# Channel.net
KiCad netlist of a schematic drawn in Altium Designer
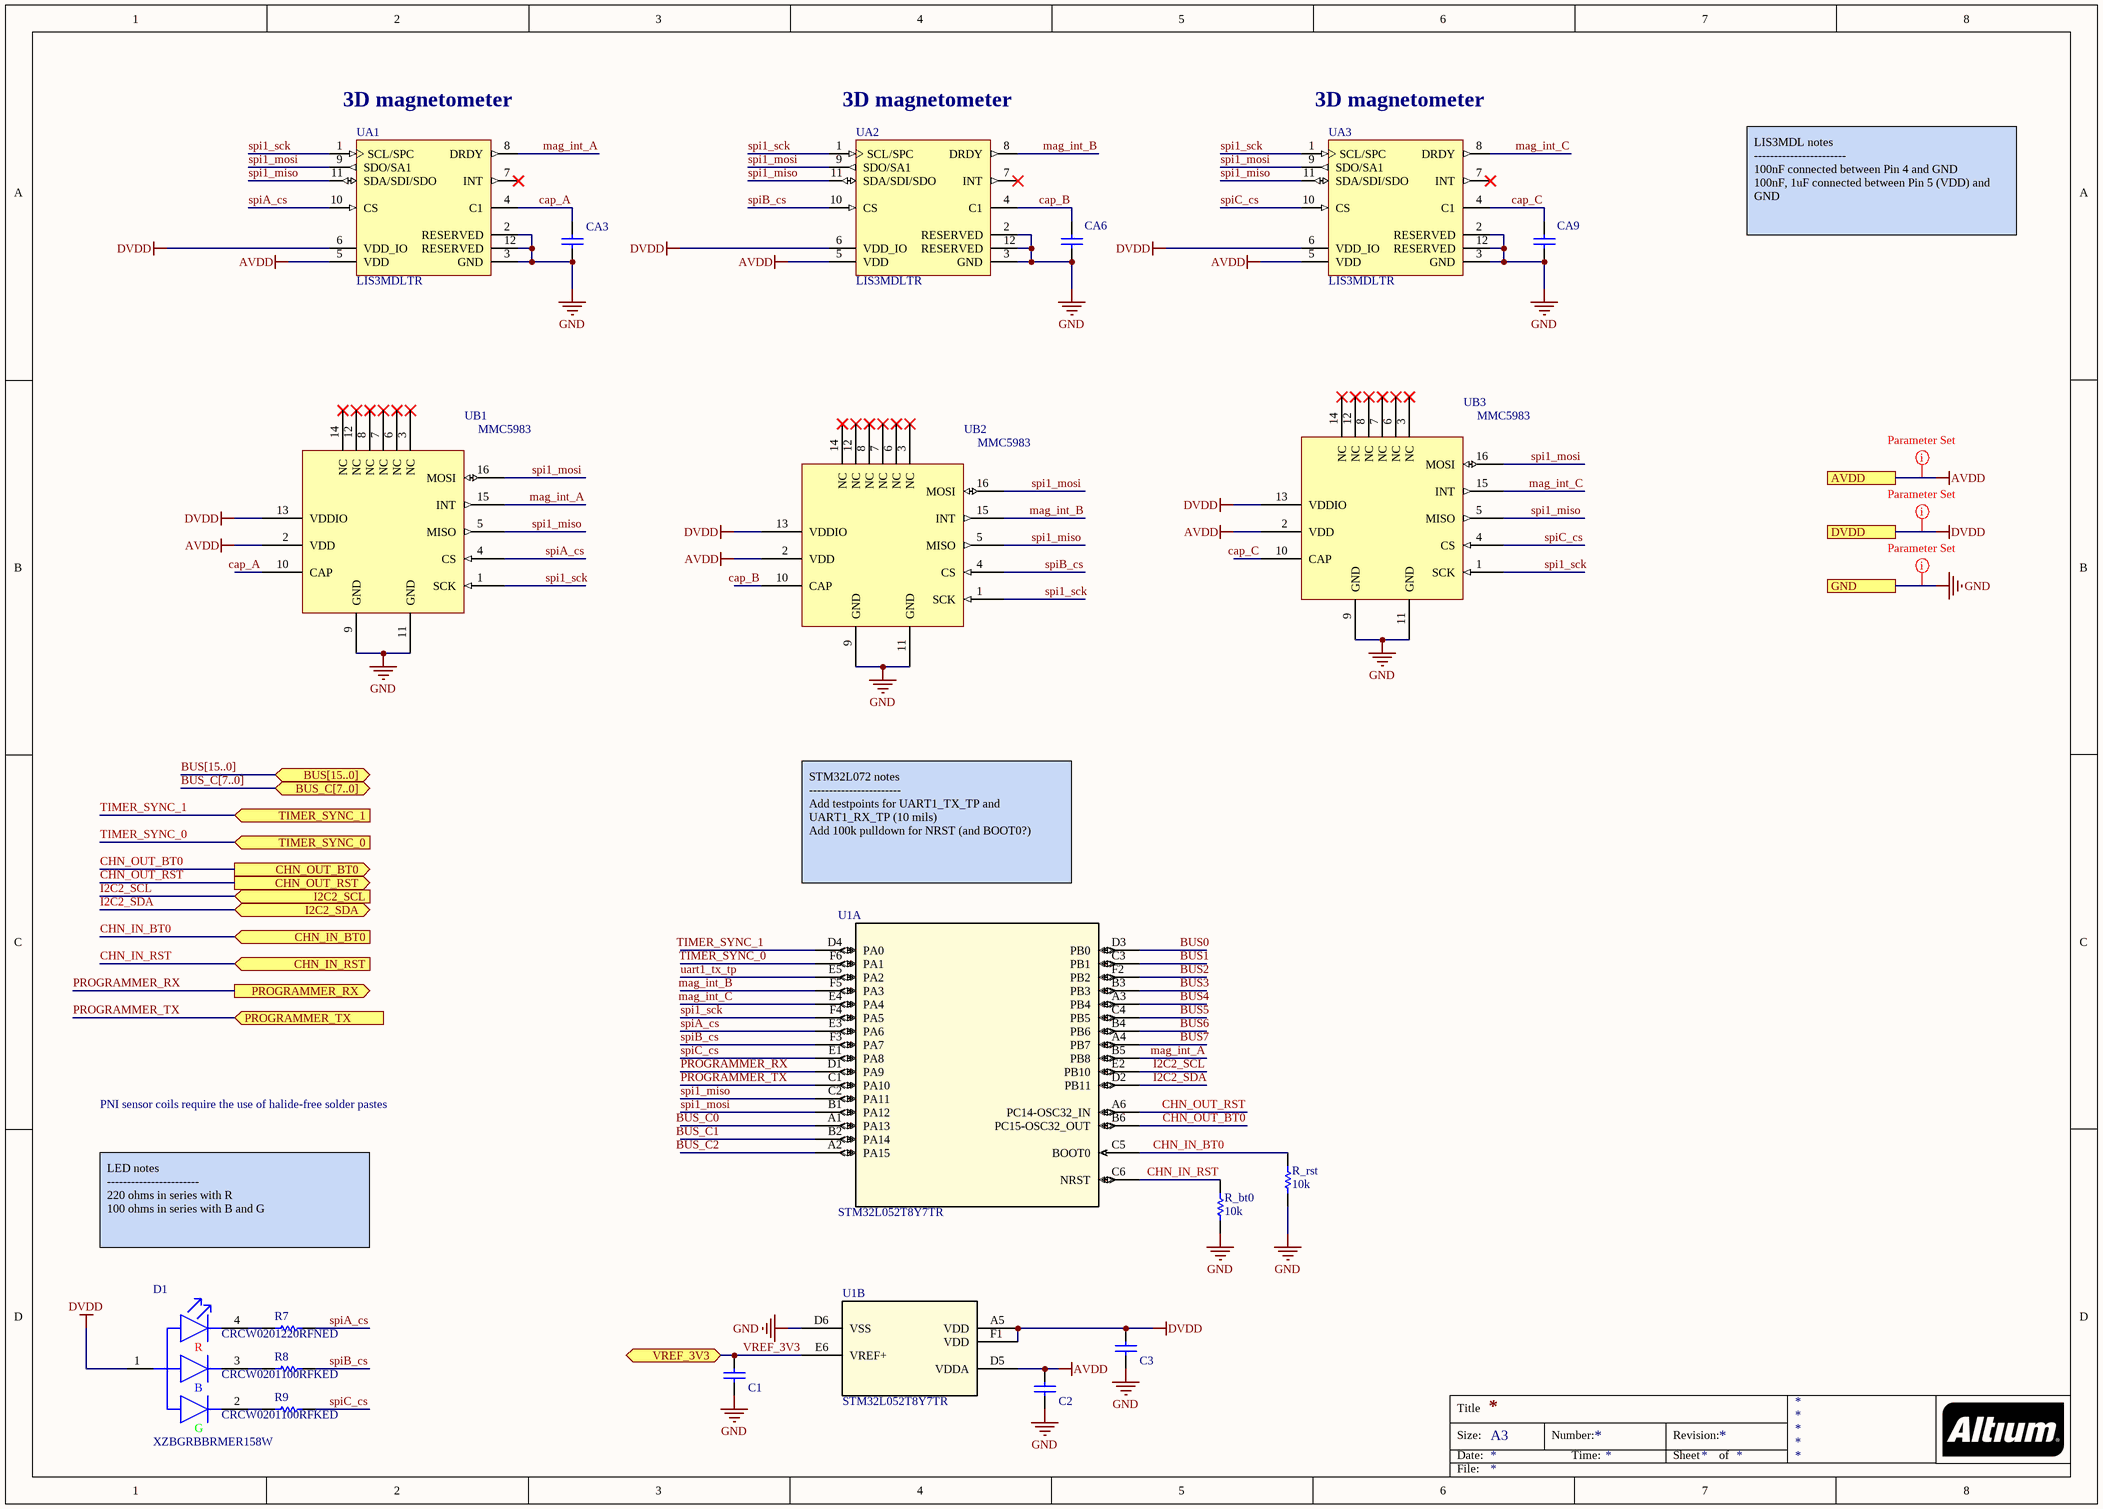
[diagram p0: Channel.SchDoc]

(export (version "E")
  (design (tool "Eeschema 10.0.6"))
  (components
    (comp (ref "C1")
      (value "GRM155R71C104KA88D")
      (footprint "CAPC1005X55X25NL05T10")
      (description "Chip Capacitor, 10 uF, +/- 10%, 6 V, -55 to 125 degC, 0402 (1005 Metric), RoHS, Tape and Reel")
      (fields (field (name "VOLTAGE") "16V") (field (name "TOLERANCE") "10%"))
      (libsource (lib "Altium Content Vault") (part "CAP-NP-2"))
    )
    (comp (ref "C2")
      (value "GRM155R71C104KA88D")
      (footprint "CAPC1005X55X25NL05T10")
      (description "Chip Capacitor, 10 uF, +/- 10%, 6 V, -55 to 125 degC, 0402 (1005 Metric), RoHS, Tape and Reel")
      (fields (field (name "VOLTAGE") "16V") (field (name "TOLERANCE") "10%"))
      (libsource (lib "Altium Content Vault") (part "CAP-NP-2"))
    )
    (comp (ref "C3")
      (value "GRM155R71C104KA88D")
      (footprint "CAPC1005X55X25NL05T10")
      (description "Chip Capacitor, 10 uF, +/- 10%, 6 V, -55 to 125 degC, 0402 (1005 Metric), RoHS, Tape and Reel")
      (fields (field (name "VOLTAGE") "16V") (field (name "TOLERANCE") "10%"))
      (libsource (lib "Altium Content Vault") (part "CAP-NP-2"))
    )
    (comp (ref "CA3")
      (value "GRM155R71C104KA88D")
      (footprint "CAPC1005X55X25NL05T10")
      (description "Chip Capacitor, 0.1 uF, +/- 10%, 16 V, -55 to 125 degC, 0402 (1005 Metric), RoHS, Tape and Reel")
      (fields (field (name "VOLTAGE") "16V") (field (name "TOLERANCE") "10%"))
      (libsource (lib "Altium Content Vault") (part "CAP-NP-2"))
    )
    (comp (ref "CA6")
      (value "GRM155R71C104KA88D")
      (footprint "CAPC1005X55X25NL05T10")
      (description "Chip Capacitor, 0.1 uF, +/- 10%, 16 V, -55 to 125 degC, 0402 (1005 Metric), RoHS, Tape and Reel")
      (fields (field (name "VOLTAGE") "16V") (field (name "TOLERANCE") "10%"))
      (libsource (lib "Altium Content Vault") (part "CAP-NP-2"))
    )
    (comp (ref "CA9")
      (value "GRM155R71C104KA88D")
      (footprint "CAPC1005X55X25NL05T10")
      (description "Chip Capacitor, 0.1 uF, +/- 10%, 16 V, -55 to 125 degC, 0402 (1005 Metric), RoHS, Tape and Reel")
      (fields (field (name "VOLTAGE") "16V") (field (name "TOLERANCE") "10%"))
      (libsource (lib "Altium Content Vault") (part "CAP-NP-2"))
    )
    (comp (ref "D1")
      (value "XZBGRBBRMER158W")
      (footprint "4-SMD")
      (description "0.65x0.65x0.20mm (0202) Full-Color Surface Mount LED")
      (libsource (lib "mantarray_library") (part "XZBGRBBRMER158W"))
    )
    (comp (ref "R7")
      (value "CRCW0201220RFNED")
      (footprint "RESC0603X28X15LL05T05")
      (fields (field (name "MANUFACTURER") "Vishay Dale"))
      (libsource (lib "Altium Content Vault") (part "RES"))
    )
    (comp (ref "R8")
      (value "CRCW0201100RFKED")
      (footprint "RESC0603X28X15LL05T05")
      (fields (field (name "MANUFACTURER") "Vishay"))
      (libsource (lib "Altium Content Vault") (part "RES"))
    )
    (comp (ref "R9")
      (value "CRCW0201100RFKED")
      (footprint "RESC0603X28X15LL05T05")
      (fields (field (name "MANUFACTURER") "Vishay"))
      (libsource (lib "Altium Content Vault") (part "RES"))
    )
    (comp (ref "R_bt0")
      (value "10k")
      (footprint "RESC0603X28X15LL05T05")
      (fields (field (name "PART NUMBER") "RC0201FR-0710KL") (field (name "MANUFACTURER") "Vishay Dale"))
      (libsource (lib "Altium Content Vault") (part "RES"))
    )
    (comp (ref "R_rst")
      (value "10k")
      (footprint "RESC0603X28X15LL05T05")
      (fields (field (name "PART NUMBER") "RC0201FR-0710KL") (field (name "MANUFACTURER") "Vishay Dale"))
      (libsource (lib "Altium Content Vault") (part "RES"))
    )
    (comp (ref "U1")
      (value "STM32L052T8Y7TR")
      (footprint "WLCSP36L_DIE417")
      (description "No Description Available")
      (fields (field (name "COPYRIGHT") "Copyright (C) 2018 Accelerated Designs. All rights reserved"))
      (libsource (lib "mantarray_library") (part "STM32L052T8Y7TR"))
    )
    (comp (ref "UA1")
      (value "LIS3MDLTR")
      (footprint "STM-LGA-12")
      (fields (field (name "MANUFACTURER") "STMicroelectronics"))
      (libsource (lib "Altium Content Vault") (part "STM-LIS3MDL-LGA-12"))
    )
    (comp (ref "UA2")
      (value "LIS3MDLTR")
      (footprint "STM-LGA-12")
      (fields (field (name "MANUFACTURER") "STMicroelectronics"))
      (libsource (lib "Altium Content Vault") (part "STM-LIS3MDL-LGA-12"))
    )
    (comp (ref "UA3")
      (value "LIS3MDLTR")
      (footprint "STM-LGA-12")
      (fields (field (name "MANUFACTURER") "STMicroelectronics"))
      (libsource (lib "Altium Content Vault") (part "STM-LIS3MDL-LGA-12"))
    )
    (comp (ref "UB1")
      (value "MMC5983")
      (footprint "mantarray_library:LGA_16")
      (description "MMC5983MA 3-axis magnetic sensor")
      (libsource (lib "1") (part "U"))
    )
    (comp (ref "UB2")
      (value "MMC5983")
      (footprint "mantarray_library:LGA_16")
      (description "MMC5983MA 3-axis magnetic sensor")
      (libsource (lib "1") (part "U"))
    )
    (comp (ref "UB3")
      (value "MMC5983")
      (footprint "mantarray_library:LGA_16")
      (description "MMC5983MA 3-axis magnetic sensor")
      (libsource (lib "1") (part "U"))
    )
  )
  (nets
    (net (code "14") (name "/BUS0") (class "Default")
      (node (ref "U1") (pin "D3") (pinfunction "PB0_D3") (pintype "bidirectional"))
    )
    (net (code "15") (name "/BUS1") (class "Default")
      (node (ref "U1") (pin "C3") (pinfunction "PB1_C3") (pintype "bidirectional"))
    )
    (net (code "16") (name "/BUS2") (class "Default")
      (node (ref "U1") (pin "F2") (pinfunction "PB2_F2") (pintype "bidirectional"))
    )
    (net (code "17") (name "/BUS3") (class "Default")
      (node (ref "U1") (pin "B3") (pinfunction "PB3_B3") (pintype "bidirectional"))
    )
    (net (code "18") (name "/BUS4") (class "Default")
      (node (ref "U1") (pin "A3") (pinfunction "PB4_A3") (pintype "bidirectional"))
    )
    (net (code "19") (name "/BUS5") (class "Default")
      (node (ref "U1") (pin "C4") (pinfunction "PB5_C4") (pintype "bidirectional"))
    )
    (net (code "20") (name "/BUS6") (class "Default")
      (node (ref "U1") (pin "B4") (pinfunction "PB6_B4") (pintype "bidirectional"))
    )
    (net (code "21") (name "/BUS7") (class "Default")
      (node (ref "U1") (pin "A4") (pinfunction "PB7_A4") (pintype "bidirectional"))
    )
    (net (code "23") (name "/BUS_C0") (class "Default")
      (node (ref "U1") (pin "A1") (pinfunction "PA13_A1") (pintype "bidirectional"))
    )
    (net (code "24") (name "/BUS_C1") (class "Default")
      (node (ref "U1") (pin "B2") (pinfunction "PA14_B2") (pintype "bidirectional"))
    )
    (net (code "25") (name "/BUS_C2") (class "Default")
      (node (ref "U1") (pin "A2") (pinfunction "PA15_A2") (pintype "bidirectional"))
    )
    (net (code "27") (name "/CHN_IN_BT0") (class "Default")
      (node (ref "R_rst") (pin "2") (pinfunction "2_2") (pintype "passive"))
      (node (ref "U1") (pin "C5") (pinfunction "BOOT0_C5") (pintype "input"))
    )
    (net (code "28") (name "/CHN_IN_RST") (class "Default")
      (node (ref "R_bt0") (pin "2") (pinfunction "2_2") (pintype "passive"))
      (node (ref "U1") (pin "C6") (pinfunction "NRST_C6") (pintype "bidirectional"))
    )
    (net (code "29") (name "/CHN_OUT_BT0") (class "Default")
      (node (ref "U1") (pin "B6") (pinfunction "PC15-OSC32_OUT_B6") (pintype "bidirectional"))
    )
    (net (code "30") (name "/CHN_OUT_RST") (class "Default")
      (node (ref "U1") (pin "A6") (pinfunction "PC14-OSC32_IN_A6") (pintype "bidirectional"))
    )
    (net (code "31") (name "/I2C2_SCL") (class "Default")
      (node (ref "U1") (pin "E2") (pinfunction "PB10_E2") (pintype "bidirectional"))
    )
    (net (code "32") (name "/I2C2_SDA") (class "Default")
      (node (ref "U1") (pin "D2") (pinfunction "PB11_D2") (pintype "bidirectional"))
    )
    (net (code "33") (name "/PROGRAMMER_RX") (class "Default")
      (node (ref "U1") (pin "D1") (pinfunction "PA9_D1") (pintype "bidirectional"))
    )
    (net (code "34") (name "/PROGRAMMER_TX") (class "Default")
      (node (ref "U1") (pin "C1") (pinfunction "PA10_C1") (pintype "bidirectional"))
    )
    (net (code "35") (name "/TIMER_SYNC_0") (class "Default")
      (node (ref "U1") (pin "F6") (pinfunction "PA1_F6") (pintype "bidirectional"))
    )
    (net (code "36") (name "/TIMER_SYNC_1") (class "Default")
      (node (ref "U1") (pin "D4") (pinfunction "PA0_D4") (pintype "bidirectional"))
    )
    (net (code "37") (name "/VREF_3V3") (class "Default")
      (node (ref "C1") (pin "2") (pinfunction "2_2") (pintype "passive"))
      (node (ref "U1") (pin "E6") (pinfunction "VREF+_E6") (pintype "power_in"))
    )
    (net (code "38") (name "/cap_A") (class "Default")
      (node (ref "CA3") (pin "2") (pinfunction "2_2") (pintype "passive"))
      (node (ref "UA1") (pin "4") (pinfunction "C1_4") (pintype "passive"))
      (node (ref "UB1") (pin "10") (pinfunction "CAP_10") (pintype "power_in"))
    )
    (net (code "39") (name "/cap_B") (class "Default")
      (node (ref "CA6") (pin "2") (pinfunction "2_2") (pintype "passive"))
      (node (ref "UA2") (pin "4") (pinfunction "C1_4") (pintype "passive"))
      (node (ref "UB2") (pin "10") (pinfunction "CAP_10") (pintype "power_in"))
    )
    (net (code "40") (name "/cap_C") (class "Default")
      (node (ref "CA9") (pin "2") (pinfunction "2_2") (pintype "passive"))
      (node (ref "UA3") (pin "4") (pinfunction "C1_4") (pintype "passive"))
      (node (ref "UB3") (pin "10") (pinfunction "CAP_10") (pintype "power_in"))
    )
    (net (code "41") (name "/mag_int_A") (class "Default")
      (node (ref "U1") (pin "B5") (pinfunction "PB8_B5") (pintype "bidirectional"))
      (node (ref "UA1") (pin "8") (pinfunction "DRDY_8") (pintype "output"))
      (node (ref "UB1") (pin "15") (pinfunction "INT_15") (pintype "output"))
    )
    (net (code "42") (name "/mag_int_B") (class "Default")
      (node (ref "U1") (pin "F5") (pinfunction "PA3_F5") (pintype "bidirectional"))
      (node (ref "UA2") (pin "8") (pinfunction "DRDY_8") (pintype "output"))
      (node (ref "UB2") (pin "15") (pinfunction "INT_15") (pintype "output"))
    )
    (net (code "43") (name "/mag_int_C") (class "Default")
      (node (ref "U1") (pin "E4") (pinfunction "PA4_E4") (pintype "bidirectional"))
      (node (ref "UA3") (pin "8") (pinfunction "DRDY_8") (pintype "output"))
      (node (ref "UB3") (pin "15") (pinfunction "INT_15") (pintype "output"))
    )
    (net (code "44") (name "/spi1_miso") (class "Default")
      (node (ref "U1") (pin "C2") (pinfunction "PA11_C2") (pintype "bidirectional"))
      (node (ref "UA1") (pin "11") (pinfunction "SDA/SDI/SDO_11") (pintype "bidirectional"))
      (node (ref "UA2") (pin "11") (pinfunction "SDA/SDI/SDO_11") (pintype "bidirectional"))
      (node (ref "UA3") (pin "11") (pinfunction "SDA/SDI/SDO_11") (pintype "bidirectional"))
      (node (ref "UB1") (pin "5") (pinfunction "MISO_5") (pintype "output"))
      (node (ref "UB2") (pin "5") (pinfunction "MISO_5") (pintype "output"))
      (node (ref "UB3") (pin "5") (pinfunction "MISO_5") (pintype "output"))
    )
    (net (code "45") (name "/spi1_mosi") (class "Default")
      (node (ref "U1") (pin "B1") (pinfunction "PA12_B1") (pintype "bidirectional"))
      (node (ref "UA1") (pin "9") (pinfunction "SDO/SA1_9") (pintype "output"))
      (node (ref "UA2") (pin "9") (pinfunction "SDO/SA1_9") (pintype "output"))
      (node (ref "UA3") (pin "9") (pinfunction "SDO/SA1_9") (pintype "output"))
      (node (ref "UB1") (pin "16") (pinfunction "MOSI_16") (pintype "bidirectional"))
      (node (ref "UB2") (pin "16") (pinfunction "MOSI_16") (pintype "bidirectional"))
      (node (ref "UB3") (pin "16") (pinfunction "MOSI_16") (pintype "bidirectional"))
    )
    (net (code "46") (name "/spi1_sck") (class "Default")
      (node (ref "U1") (pin "F4") (pinfunction "PA5_F4") (pintype "bidirectional"))
      (node (ref "UA1") (pin "1") (pinfunction "SCL/SPC_1") (pintype "input"))
      (node (ref "UA2") (pin "1") (pinfunction "SCL/SPC_1") (pintype "input"))
      (node (ref "UA3") (pin "1") (pinfunction "SCL/SPC_1") (pintype "input"))
      (node (ref "UB1") (pin "1") (pinfunction "SCK_1") (pintype "input"))
      (node (ref "UB2") (pin "1") (pinfunction "SCK_1") (pintype "input"))
      (node (ref "UB3") (pin "1") (pinfunction "SCK_1") (pintype "input"))
    )
    (net (code "47") (name "/spiA_cs") (class "Default")
      (node (ref "R7") (pin "2") (pinfunction "2_2") (pintype "passive"))
      (node (ref "U1") (pin "E3") (pinfunction "PA6_E3") (pintype "bidirectional"))
      (node (ref "UA1") (pin "10") (pinfunction "CS_10") (pintype "input"))
      (node (ref "UB1") (pin "4") (pinfunction "CS_4") (pintype "input"))
    )
    (net (code "48") (name "/spiB_cs") (class "Default")
      (node (ref "R8") (pin "2") (pinfunction "2_2") (pintype "passive"))
      (node (ref "U1") (pin "F3") (pinfunction "PA7_F3") (pintype "bidirectional"))
      (node (ref "UA2") (pin "10") (pinfunction "CS_10") (pintype "input"))
      (node (ref "UB2") (pin "4") (pinfunction "CS_4") (pintype "input"))
    )
    (net (code "49") (name "/spiC_cs") (class "Default")
      (node (ref "R9") (pin "2") (pinfunction "2_2") (pintype "passive"))
      (node (ref "U1") (pin "E1") (pinfunction "PA8_E1") (pintype "bidirectional"))
      (node (ref "UA3") (pin "10") (pinfunction "CS_10") (pintype "input"))
      (node (ref "UB3") (pin "4") (pinfunction "CS_4") (pintype "input"))
    )
    (net (code "50") (name "/uart1_tx_tp") (class "Default")
      (node (ref "U1") (pin "E5") (pinfunction "PA2_E5") (pintype "bidirectional"))
    )
    (net (code "51") (name "AVDD") (class "Default")
      (node (ref "C2") (pin "2") (pinfunction "2_2") (pintype "passive"))
      (node (ref "U1") (pin "D5") (pinfunction "VDDA_D5") (pintype "power_in"))
      (node (ref "UA1") (pin "5") (pinfunction "VDD_5") (pintype "power_in"))
      (node (ref "UA2") (pin "5") (pinfunction "VDD_5") (pintype "power_in"))
      (node (ref "UA3") (pin "5") (pinfunction "VDD_5") (pintype "power_in"))
      (node (ref "UB1") (pin "2") (pinfunction "VDD_2") (pintype "power_in"))
      (node (ref "UB2") (pin "2") (pinfunction "VDD_2") (pintype "power_in"))
      (node (ref "UB3") (pin "2") (pinfunction "VDD_2") (pintype "power_in"))
    )
    (net (code "52") (name "DVDD") (class "Default")
      (node (ref "C3") (pin "2") (pinfunction "2_2") (pintype "passive"))
      (node (ref "D1") (pin "1") (pinfunction "1_1") (pintype "passive"))
      (node (ref "U1") (pin "A5") (pinfunction "VDD_A5") (pintype "power_in"))
      (node (ref "U1") (pin "F1") (pinfunction "VDD_F1") (pintype "power_in"))
      (node (ref "UA1") (pin "6") (pinfunction "VDD_IO_6") (pintype "power_in"))
      (node (ref "UA2") (pin "6") (pinfunction "VDD_IO_6") (pintype "power_in"))
      (node (ref "UA3") (pin "6") (pinfunction "VDD_IO_6") (pintype "power_in"))
      (node (ref "UB1") (pin "13") (pinfunction "VDDIO_13") (pintype "power_in"))
      (node (ref "UB2") (pin "13") (pinfunction "VDDIO_13") (pintype "power_in"))
      (node (ref "UB3") (pin "13") (pinfunction "VDDIO_13") (pintype "power_in"))
    )
    (net (code "53") (name "GND") (class "Default")
      (node (ref "C1") (pin "1") (pinfunction "1_1") (pintype "passive"))
      (node (ref "C2") (pin "1") (pinfunction "1_1") (pintype "passive"))
      (node (ref "C3") (pin "1") (pinfunction "1_1") (pintype "passive"))
      (node (ref "CA3") (pin "1") (pinfunction "1_1") (pintype "passive"))
      (node (ref "CA6") (pin "1") (pinfunction "1_1") (pintype "passive"))
      (node (ref "CA9") (pin "1") (pinfunction "1_1") (pintype "passive"))
      (node (ref "R_bt0") (pin "1") (pinfunction "1_1") (pintype "passive"))
      (node (ref "R_rst") (pin "1") (pinfunction "1_1") (pintype "passive"))
      (node (ref "U1") (pin "D6") (pinfunction "VSS_D6") (pintype "power_in"))
      (node (ref "UA1") (pin "12") (pinfunction "RESERVED_12") (pintype "passive"))
      (node (ref "UA1") (pin "2") (pinfunction "RESERVED_2") (pintype "passive"))
      (node (ref "UA1") (pin "3") (pinfunction "GND_3") (pintype "power_in"))
      (node (ref "UA2") (pin "12") (pinfunction "RESERVED_12") (pintype "passive"))
      (node (ref "UA2") (pin "2") (pinfunction "RESERVED_2") (pintype "passive"))
      (node (ref "UA2") (pin "3") (pinfunction "GND_3") (pintype "power_in"))
      (node (ref "UA3") (pin "12") (pinfunction "RESERVED_12") (pintype "passive"))
      (node (ref "UA3") (pin "2") (pinfunction "RESERVED_2") (pintype "passive"))
      (node (ref "UA3") (pin "3") (pinfunction "GND_3") (pintype "power_in"))
      (node (ref "UB1") (pin "11") (pinfunction "GND_11") (pintype "power_in"))
      (node (ref "UB1") (pin "9") (pinfunction "GND_9") (pintype "power_in"))
      (node (ref "UB2") (pin "11") (pinfunction "GND_11") (pintype "power_in"))
      (node (ref "UB2") (pin "9") (pinfunction "GND_9") (pintype "power_in"))
      (node (ref "UB3") (pin "11") (pinfunction "GND_11") (pintype "power_in"))
      (node (ref "UB3") (pin "9") (pinfunction "GND_9") (pintype "power_in"))
    )
    (net (code "54") (name "Net-(D1-Pad2)") (class "Default")
      (node (ref "D1") (pin "2") (pinfunction "2_2") (pintype "passive"))
      (node (ref "R9") (pin "1") (pinfunction "1_1") (pintype "passive"))
    )
    (net (code "55") (name "Net-(D1-Pad3)") (class "Default")
      (node (ref "D1") (pin "3") (pinfunction "3_3") (pintype "passive"))
      (node (ref "R8") (pin "1") (pinfunction "1_1") (pintype "passive"))
    )
    (net (code "56") (name "Net-(D1-Pad4)") (class "Default")
      (node (ref "D1") (pin "4") (pinfunction "4_4") (pintype "passive"))
      (node (ref "R7") (pin "1") (pinfunction "1_1") (pintype "passive"))
    )
    (net (code "57") (name "unconnected-(UA1-INT-Pad7)") (class "Default")
      (node (ref "UA1") (pin "7") (pinfunction "INT_7") (pintype "output+no_connect"))
    )
    (net (code "58") (name "unconnected-(UA2-INT-Pad7)") (class "Default")
      (node (ref "UA2") (pin "7") (pinfunction "INT_7") (pintype "output+no_connect"))
    )
    (net (code "59") (name "unconnected-(UA3-INT-Pad7)") (class "Default")
      (node (ref "UA3") (pin "7") (pinfunction "INT_7") (pintype "output+no_connect"))
    )
    (net (code "60") (name "unconnected-(UB1-NC-Pad3)") (class "Default")
      (node (ref "UB1") (pin "3") (pinfunction "NC_3") (pintype "passive+no_connect"))
    )
    (net (code "61") (name "unconnected-(UB1-NC-Pad6)") (class "Default")
      (node (ref "UB1") (pin "6") (pinfunction "NC_6") (pintype "passive+no_connect"))
    )
    (net (code "62") (name "unconnected-(UB1-NC-Pad7)") (class "Default")
      (node (ref "UB1") (pin "7") (pinfunction "NC_7") (pintype "passive+no_connect"))
    )
    (net (code "63") (name "unconnected-(UB1-NC-Pad8)") (class "Default")
      (node (ref "UB1") (pin "8") (pinfunction "NC_8") (pintype "passive+no_connect"))
    )
    (net (code "64") (name "unconnected-(UB1-NC-Pad12)") (class "Default")
      (node (ref "UB1") (pin "12") (pinfunction "NC_12") (pintype "passive+no_connect"))
    )
    (net (code "65") (name "unconnected-(UB1-NC-Pad14)") (class "Default")
      (node (ref "UB1") (pin "14") (pinfunction "NC_14") (pintype "passive+no_connect"))
    )
    (net (code "66") (name "unconnected-(UB2-NC-Pad3)") (class "Default")
      (node (ref "UB2") (pin "3") (pinfunction "NC_3") (pintype "passive+no_connect"))
    )
    (net (code "67") (name "unconnected-(UB2-NC-Pad6)") (class "Default")
      (node (ref "UB2") (pin "6") (pinfunction "NC_6") (pintype "passive+no_connect"))
    )
    (net (code "68") (name "unconnected-(UB2-NC-Pad7)") (class "Default")
      (node (ref "UB2") (pin "7") (pinfunction "NC_7") (pintype "passive+no_connect"))
    )
    (net (code "69") (name "unconnected-(UB2-NC-Pad8)") (class "Default")
      (node (ref "UB2") (pin "8") (pinfunction "NC_8") (pintype "passive+no_connect"))
    )
    (net (code "70") (name "unconnected-(UB2-NC-Pad12)") (class "Default")
      (node (ref "UB2") (pin "12") (pinfunction "NC_12") (pintype "passive+no_connect"))
    )
    (net (code "71") (name "unconnected-(UB2-NC-Pad14)") (class "Default")
      (node (ref "UB2") (pin "14") (pinfunction "NC_14") (pintype "passive+no_connect"))
    )
    (net (code "72") (name "unconnected-(UB3-NC-Pad3)") (class "Default")
      (node (ref "UB3") (pin "3") (pinfunction "NC_3") (pintype "passive+no_connect"))
    )
    (net (code "73") (name "unconnected-(UB3-NC-Pad6)") (class "Default")
      (node (ref "UB3") (pin "6") (pinfunction "NC_6") (pintype "passive+no_connect"))
    )
    (net (code "74") (name "unconnected-(UB3-NC-Pad7)") (class "Default")
      (node (ref "UB3") (pin "7") (pinfunction "NC_7") (pintype "passive+no_connect"))
    )
    (net (code "75") (name "unconnected-(UB3-NC-Pad8)") (class "Default")
      (node (ref "UB3") (pin "8") (pinfunction "NC_8") (pintype "passive+no_connect"))
    )
    (net (code "76") (name "unconnected-(UB3-NC-Pad12)") (class "Default")
      (node (ref "UB3") (pin "12") (pinfunction "NC_12") (pintype "passive+no_connect"))
    )
    (net (code "77") (name "unconnected-(UB3-NC-Pad14)") (class "Default")
      (node (ref "UB3") (pin "14") (pinfunction "NC_14") (pintype "passive+no_connect"))
    )
  )
)
